# 100Wdriver.net
KiCad netlist of a schematic drawn in EAGLE
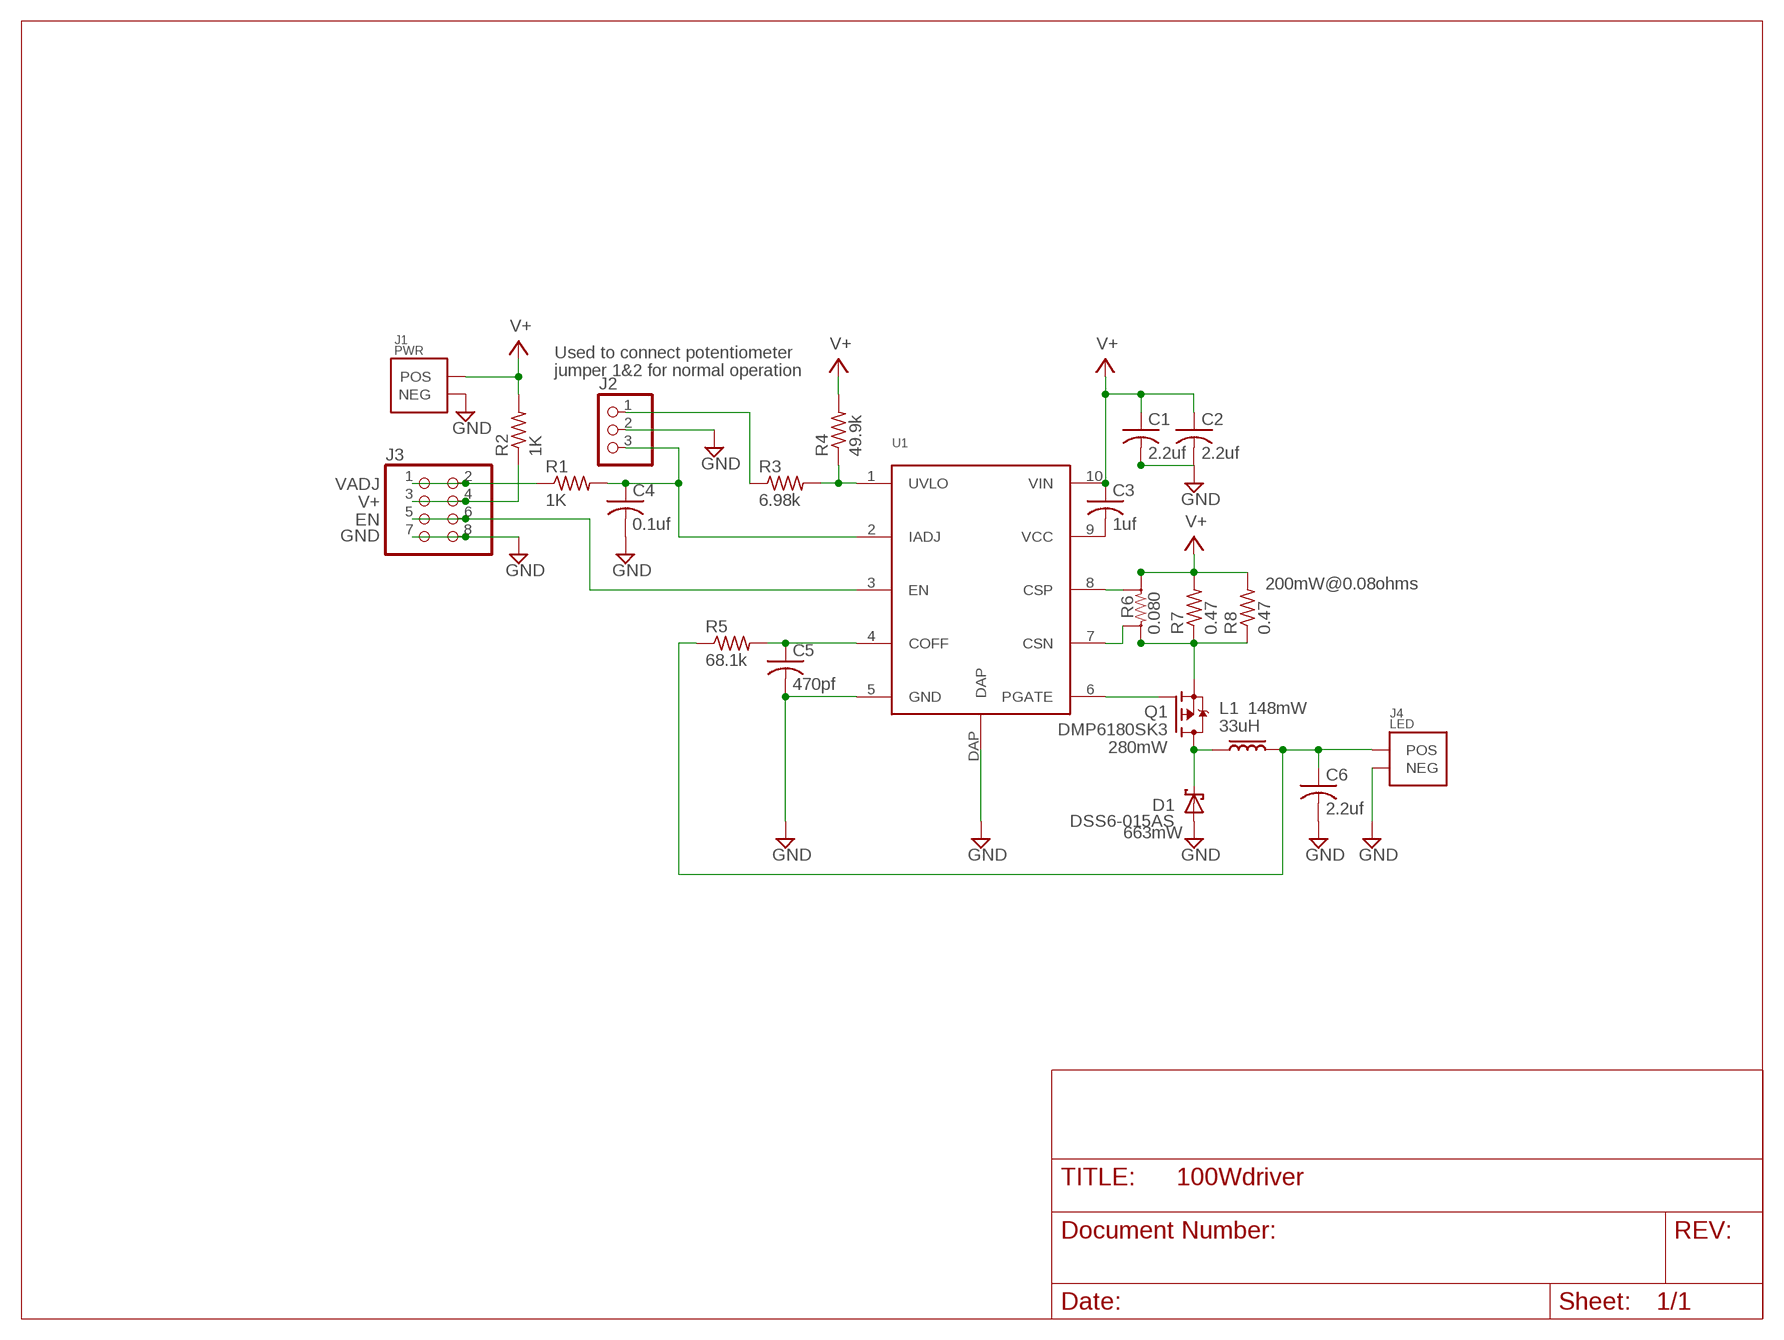
[diagram p0: schematic, sheet 1]

(export (version "E")
  (design (tool "Eeschema 10.0.6"))
  (components
    (comp (ref "C1")
      (value "2.2uf")
      (footprint "eagle-import:C1210")
      (libsource (lib "eagle-import") (part "C-USC1210"))
    )
    (comp (ref "C2")
      (value "2.2uf")
      (footprint "eagle-import:C1210")
      (libsource (lib "eagle-import") (part "C-USC1210"))
    )
    (comp (ref "C3")
      (value "1uf")
      (footprint "eagle-import:C0805")
      (libsource (lib "eagle-import") (part "C-USC0805"))
    )
    (comp (ref "C4")
      (value "0.1uf")
      (footprint "eagle-import:C0805")
      (libsource (lib "eagle-import") (part "C-USC0805"))
    )
    (comp (ref "C5")
      (value "470pf")
      (footprint "eagle-import:C0805")
      (libsource (lib "eagle-import") (part "C-USC0805"))
    )
    (comp (ref "C6")
      (value "2.2uf")
      (footprint "eagle-import:C1210")
      (libsource (lib "eagle-import") (part "C-USC1210"))
    )
    (comp (ref "D1")
      (value "DSS6-015AS")
      (footprint "eagle-import:D-PAK_TO252AA")
      (libsource (lib "eagle-import") (part "BZW04XX"))
    )
    (comp (ref "J1")
      (value "PWR")
      (footprint "eagle-import:3.5MMLEFT")
      (libsource (lib "eagle-import") (part "TERMBLOCKLEFT"))
    )
    (comp (ref "J2")
      (value "PINHD-1X3")
      (footprint "eagle-import:1X03")
      (libsource (lib "eagle-import") (part "PINHD-1X3"))
    )
    (comp (ref "J3")
      (value "PINHD-2X4")
      (footprint "eagle-import:2X04")
      (libsource (lib "eagle-import") (part "PINHD-2X4"))
    )
    (comp (ref "J4")
      (value "LED")
      (footprint "eagle-import:3.5MM")
      (libsource (lib "eagle-import") (part "TERMBLOCK"))
    )
    (comp (ref "L1")
      (value "33uH")
      (footprint "eagle-import:SDR2207")
      (libsource (lib "eagle-import") (part "SDR2207"))
    )
    (comp (ref "Q1")
      (value "DMP6180SK3")
      (footprint "eagle-import:TO252")
      (libsource (lib "eagle-import") (part "FDD4141TO252"))
    )
    (comp (ref "R1")
      (value "1K")
      (footprint "eagle-import:R0805")
      (libsource (lib "eagle-import") (part "R-US_R0805"))
    )
    (comp (ref "R2")
      (value "1K")
      (footprint "eagle-import:R0805")
      (libsource (lib "eagle-import") (part "R-US_R0805"))
    )
    (comp (ref "R3")
      (value "6.98k")
      (footprint "eagle-import:R0805")
      (libsource (lib "eagle-import") (part "R-US_R0805"))
    )
    (comp (ref "R4")
      (value "49.9k")
      (footprint "eagle-import:R0805")
      (libsource (lib "eagle-import") (part "R-US_R0805"))
    )
    (comp (ref "R5")
      (value "68.1k")
      (footprint "eagle-import:R0805")
      (libsource (lib "eagle-import") (part "R-US_R0805"))
    )
    (comp (ref "R6")
      (value "0.080")
      (footprint "eagle-import:2512SENSE")
      (libsource (lib "eagle-import") (part "RSNS2512"))
    )
    (comp (ref "R7")
      (value "0.47")
      (footprint "eagle-import:R1206")
      (libsource (lib "eagle-import") (part "R-US_R1206"))
    )
    (comp (ref "R8")
      (value "0.47")
      (footprint "eagle-import:R1206")
      (libsource (lib "eagle-import") (part "R-US_R1206"))
    )
    (comp (ref "U1")
      (value "LM3409HV")
      (footprint "eagle-import:10VSSOP")
      (libsource (lib "eagle-import") (part "LM3409HV"))
    )
  )
  (nets
    (net (code "1") (name "GND") (class "Default")
      (node (ref "C1") (pin "2") (pinfunction "2_2") (pintype "passive"))
      (node (ref "C2") (pin "2") (pinfunction "2_2") (pintype "passive"))
      (node (ref "C4") (pin "2") (pinfunction "2_2") (pintype "passive"))
      (node (ref "C5") (pin "2") (pinfunction "2_2") (pintype "passive"))
      (node (ref "C6") (pin "2") (pinfunction "2_2") (pintype "passive"))
      (node (ref "D1") (pin "1") (pinfunction "A_1") (pintype "passive"))
      (node (ref "D1") (pin "3") (pinfunction "A_3") (pintype "passive"))
      (node (ref "J1") (pin "GND") (pinfunction "NEG_GND") (pintype "bidirectional"))
      (node (ref "J2") (pin "2") (pinfunction "2_2") (pintype "passive"))
      (node (ref "J3") (pin "7") (pinfunction "7_7") (pintype "passive"))
      (node (ref "J3") (pin "8") (pinfunction "8_8") (pintype "passive"))
      (node (ref "J4") (pin "NEGATIVE") (pinfunction "NEG_NEGATIVE") (pintype "bidirectional"))
      (node (ref "U1") (pin "5") (pinfunction "GND_5") (pintype "bidirectional"))
      (node (ref "U1") (pin "DAP") (pinfunction "DAP_DAP") (pintype "bidirectional"))
    )
    (net (code "2") (name "Net-(D1-C)") (class "Default")
      (node (ref "D1") (pin "4") (pinfunction "C_4") (pintype "passive"))
      (node (ref "L1") (pin "P$1") (pinfunction "P$1_P$1") (pintype "bidirectional"))
      (node (ref "Q1") (pin "3") (pinfunction "D_3") (pintype "passive"))
    )
    (net (code "3") (name "Net-(J2-Pad1)") (class "Default")
      (node (ref "J2") (pin "1") (pinfunction "1_1") (pintype "passive"))
      (node (ref "R3") (pin "1") (pinfunction "1_1") (pintype "passive"))
    )
    (net (code "4") (name "Net-(J3-Pad1)") (class "Default")
      (node (ref "J3") (pin "1") (pinfunction "1_1") (pintype "passive"))
      (node (ref "J3") (pin "2") (pinfunction "2_2") (pintype "passive"))
      (node (ref "R1") (pin "1") (pinfunction "1_1") (pintype "passive"))
    )
    (net (code "5") (name "Net-(J3-Pad3)") (class "Default")
      (node (ref "J3") (pin "3") (pinfunction "3_3") (pintype "passive"))
      (node (ref "J3") (pin "4") (pinfunction "4_4") (pintype "passive"))
      (node (ref "R2") (pin "1") (pinfunction "1_1") (pintype "passive"))
    )
    (net (code "6") (name "Net-(J4-POS)") (class "Default")
      (node (ref "C6") (pin "1") (pinfunction "1_1") (pintype "passive"))
      (node (ref "J4") (pin "POSITIVE") (pinfunction "POS_POSITIVE") (pintype "bidirectional"))
      (node (ref "L1") (pin "P$2") (pinfunction "P$2_P$2") (pintype "bidirectional"))
      (node (ref "R5") (pin "1") (pinfunction "1_1") (pintype "passive"))
    )
    (net (code "7") (name "Net-(Q1-G)") (class "Default")
      (node (ref "Q1") (pin "1") (pinfunction "G_1") (pintype "passive"))
      (node (ref "U1") (pin "6") (pinfunction "PGATE_6") (pintype "bidirectional"))
    )
    (net (code "8") (name "Net-(Q1-S)") (class "Default")
      (node (ref "Q1") (pin "2") (pinfunction "S_2") (pintype "passive"))
      (node (ref "R6") (pin "P$3") (pinfunction "P$3_P$3") (pintype "bidirectional"))
      (node (ref "R6") (pin "P$4") (pinfunction "P$4_P$4") (pintype "bidirectional"))
      (node (ref "R7") (pin "1") (pinfunction "1_1") (pintype "passive"))
      (node (ref "R8") (pin "1") (pinfunction "1_1") (pintype "passive"))
    )
    (net (code "9") (name "Net-(U1-COFF)") (class "Default")
      (node (ref "C5") (pin "1") (pinfunction "1_1") (pintype "passive"))
      (node (ref "R5") (pin "2") (pinfunction "2_2") (pintype "passive"))
      (node (ref "U1") (pin "4") (pinfunction "COFF_4") (pintype "bidirectional"))
    )
    (net (code "10") (name "Net-(U1-CSN)") (class "Default")
      (node (ref "R6") (pin "SNS2") (pinfunction "SNS2_SNS2") (pintype "bidirectional"))
      (node (ref "U1") (pin "7") (pinfunction "CSN_7") (pintype "bidirectional"))
    )
    (net (code "11") (name "Net-(U1-CSP)") (class "Default")
      (node (ref "R6") (pin "SNS1") (pinfunction "SNS1_SNS1") (pintype "bidirectional"))
      (node (ref "U1") (pin "8") (pinfunction "CSP_8") (pintype "bidirectional"))
    )
    (net (code "12") (name "Net-(U1-EN)") (class "Default")
      (node (ref "J3") (pin "5") (pinfunction "5_5") (pintype "passive"))
      (node (ref "J3") (pin "6") (pinfunction "6_6") (pintype "passive"))
      (node (ref "U1") (pin "3") (pinfunction "EN_3") (pintype "bidirectional"))
    )
    (net (code "13") (name "Net-(U1-IADJ)") (class "Default")
      (node (ref "C4") (pin "1") (pinfunction "1_1") (pintype "passive"))
      (node (ref "J2") (pin "3") (pinfunction "3_3") (pintype "passive"))
      (node (ref "R1") (pin "2") (pinfunction "2_2") (pintype "passive"))
      (node (ref "U1") (pin "2") (pinfunction "IADJ_2") (pintype "bidirectional"))
    )
    (net (code "14") (name "Net-(U1-UVLO)") (class "Default")
      (node (ref "R3") (pin "2") (pinfunction "2_2") (pintype "passive"))
      (node (ref "R4") (pin "1") (pinfunction "1_1") (pintype "passive"))
      (node (ref "U1") (pin "1") (pinfunction "UVLO_1") (pintype "bidirectional"))
    )
    (net (code "15") (name "Net-(U1-VCC)") (class "Default")
      (node (ref "C3") (pin "2") (pinfunction "2_2") (pintype "passive"))
      (node (ref "U1") (pin "9") (pinfunction "VCC_9") (pintype "bidirectional"))
    )
    (net (code "16") (name "V+") (class "Default")
      (node (ref "C1") (pin "1") (pinfunction "1_1") (pintype "passive"))
      (node (ref "C2") (pin "1") (pinfunction "1_1") (pintype "passive"))
      (node (ref "C3") (pin "1") (pinfunction "1_1") (pintype "passive"))
      (node (ref "J1") (pin "V+") (pinfunction "POS_V+") (pintype "bidirectional"))
      (node (ref "R2") (pin "2") (pinfunction "2_2") (pintype "passive"))
      (node (ref "R4") (pin "2") (pinfunction "2_2") (pintype "passive"))
      (node (ref "R6") (pin "P$1") (pinfunction "P$1_P$1") (pintype "bidirectional"))
      (node (ref "R6") (pin "P$2") (pinfunction "P$2_P$2") (pintype "bidirectional"))
      (node (ref "R7") (pin "2") (pinfunction "2_2") (pintype "passive"))
      (node (ref "R8") (pin "2") (pinfunction "2_2") (pintype "passive"))
      (node (ref "U1") (pin "10") (pinfunction "VIN_10") (pintype "bidirectional"))
    )
  )
)
